# hybri.net
KiCad netlist of a schematic drawn in EAGLE
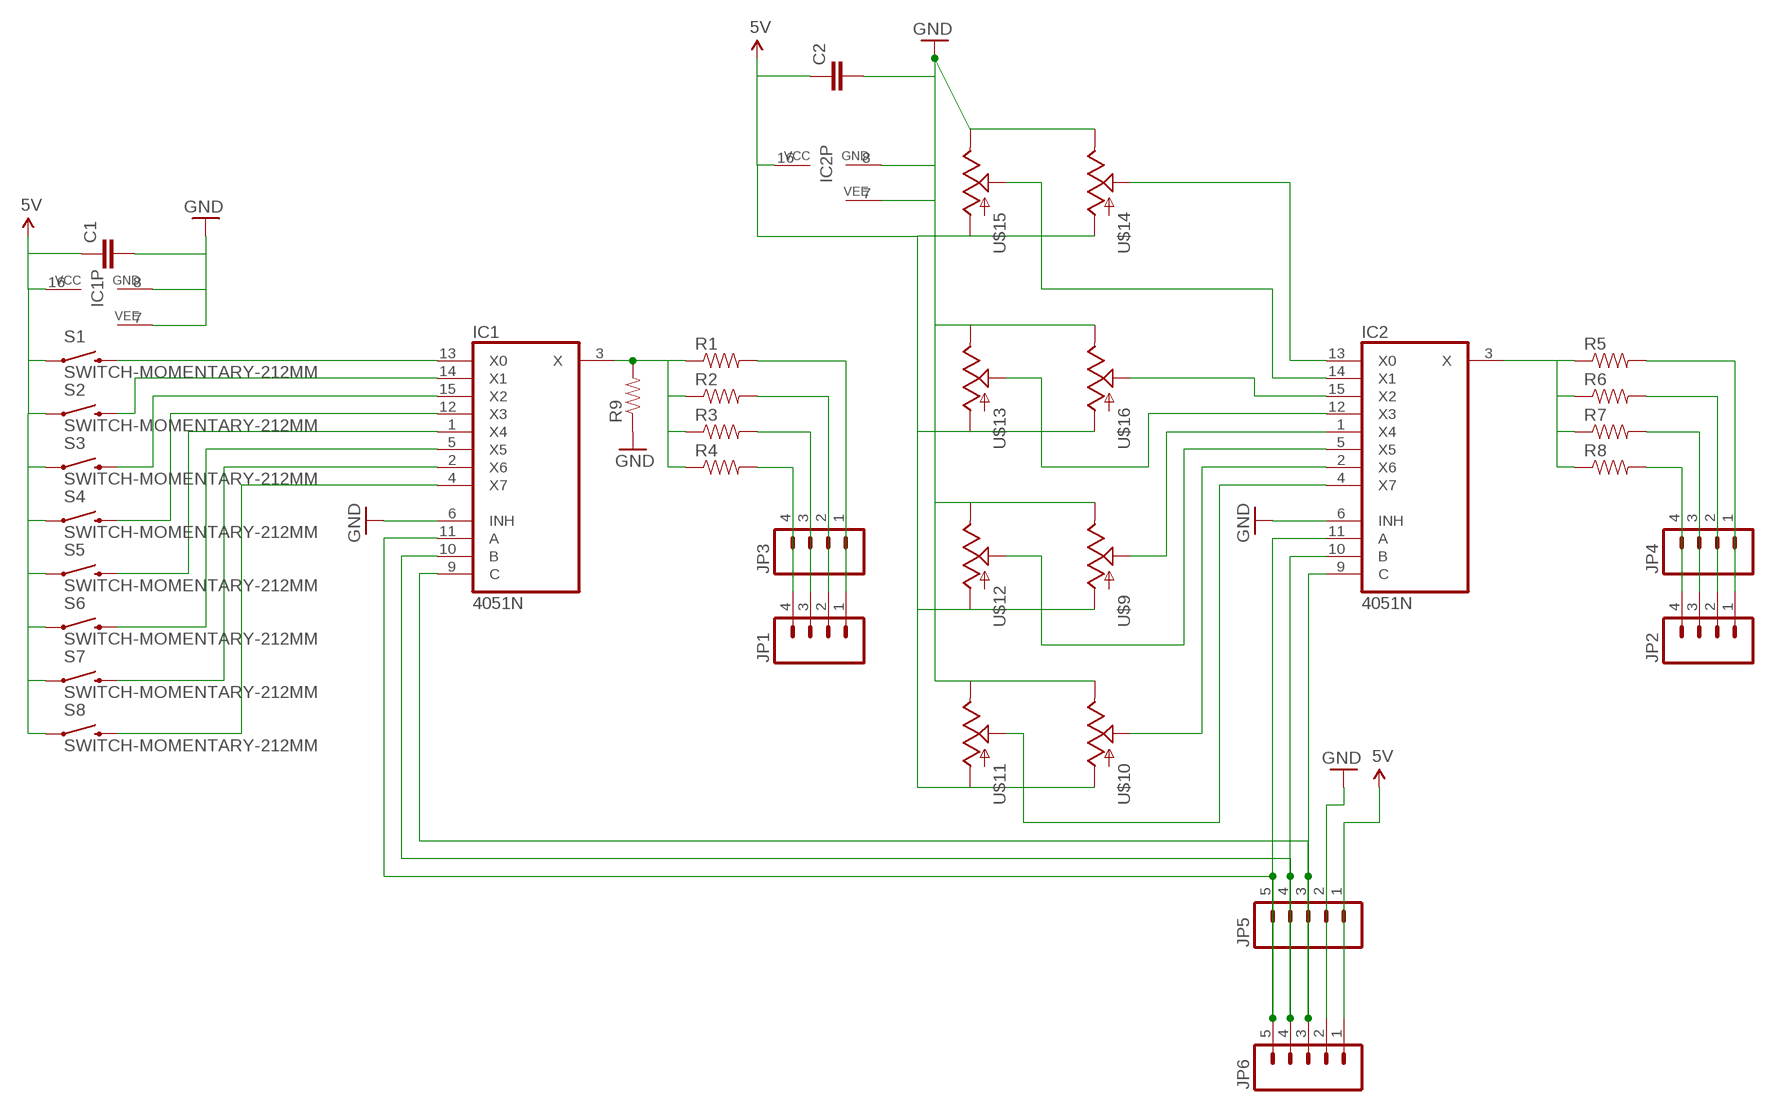
[diagram p0: schematic, sheet 1]

(export (version "E")
  (design (tool "Eeschema 10.0.6"))
  (components
    (comp (ref "C1")
      (value "CAPPTH")
      (footprint "eagle-import:CAP-PTH-SMALL")
      (libsource (lib "eagle-import") (part "CAPPTH"))
    )
    (comp (ref "C2")
      (value "CAPPTH")
      (footprint "eagle-import:CAP-PTH-SMALL")
      (libsource (lib "eagle-import") (part "CAPPTH"))
    )
    (comp (ref "IC1")
      (value "4051N")
      (footprint "eagle-import:DIL16")
      (libsource (lib "eagle-import") (part "4051N"))
    )
    (comp (ref "IC2")
      (value "4051N")
      (footprint "eagle-import:DIL16")
      (libsource (lib "eagle-import") (part "4051N"))
    )
    (comp (ref "JP1")
      (value "M04PTH")
      (footprint "eagle-import:1X04")
      (libsource (lib "eagle-import") (part "M04PTH"))
    )
    (comp (ref "JP2")
      (value "M04PTH")
      (footprint "eagle-import:1X04")
      (libsource (lib "eagle-import") (part "M04PTH"))
    )
    (comp (ref "JP3")
      (value "M04PTH")
      (footprint "eagle-import:1X04")
      (libsource (lib "eagle-import") (part "M04PTH"))
    )
    (comp (ref "JP4")
      (value "M04PTH")
      (footprint "eagle-import:1X04")
      (libsource (lib "eagle-import") (part "M04PTH"))
    )
    (comp (ref "JP5")
      (value "M05PTH")
      (footprint "eagle-import:1X05")
      (libsource (lib "eagle-import") (part "M05PTH"))
    )
    (comp (ref "JP6")
      (value "M05PTH")
      (footprint "eagle-import:1X05")
      (libsource (lib "eagle-import") (part "M05PTH"))
    )
    (comp (ref "R1")
      (value "RESISTORAXIAL-0.3")
      (footprint "eagle-import:AXIAL-0.3")
      (libsource (lib "eagle-import") (part "RESISTORAXIAL-0.3"))
    )
    (comp (ref "R2")
      (value "RESISTORAXIAL-0.3")
      (footprint "eagle-import:AXIAL-0.3")
      (libsource (lib "eagle-import") (part "RESISTORAXIAL-0.3"))
    )
    (comp (ref "R3")
      (value "RESISTORAXIAL-0.3")
      (footprint "eagle-import:AXIAL-0.3")
      (libsource (lib "eagle-import") (part "RESISTORAXIAL-0.3"))
    )
    (comp (ref "R4")
      (value "RESISTORAXIAL-0.3")
      (footprint "eagle-import:AXIAL-0.3")
      (libsource (lib "eagle-import") (part "RESISTORAXIAL-0.3"))
    )
    (comp (ref "R5")
      (value "RESISTORAXIAL-0.3")
      (footprint "eagle-import:AXIAL-0.3")
      (libsource (lib "eagle-import") (part "RESISTORAXIAL-0.3"))
    )
    (comp (ref "R6")
      (value "RESISTORAXIAL-0.3")
      (footprint "eagle-import:AXIAL-0.3")
      (libsource (lib "eagle-import") (part "RESISTORAXIAL-0.3"))
    )
    (comp (ref "R7")
      (value "RESISTORAXIAL-0.3")
      (footprint "eagle-import:AXIAL-0.3")
      (libsource (lib "eagle-import") (part "RESISTORAXIAL-0.3"))
    )
    (comp (ref "R8")
      (value "RESISTORAXIAL-0.3")
      (footprint "eagle-import:AXIAL-0.3")
      (libsource (lib "eagle-import") (part "RESISTORAXIAL-0.3"))
    )
    (comp (ref "R9")
      (value "RESISTORAXIAL-0.3")
      (footprint "eagle-import:AXIAL-0.3")
      (libsource (lib "eagle-import") (part "RESISTORAXIAL-0.3"))
    )
    (comp (ref "S1")
      (value "SWITCH-MOMENTARY-212MM")
      (footprint "eagle-import:TACTILE-PTH-12MM")
      (libsource (lib "eagle-import") (part "SWITCH-MOMENTARY-212MM"))
    )
    (comp (ref "S2")
      (value "SWITCH-MOMENTARY-212MM")
      (footprint "eagle-import:TACTILE-PTH-12MM")
      (libsource (lib "eagle-import") (part "SWITCH-MOMENTARY-212MM"))
    )
    (comp (ref "S3")
      (value "SWITCH-MOMENTARY-212MM")
      (footprint "eagle-import:TACTILE-PTH-12MM")
      (libsource (lib "eagle-import") (part "SWITCH-MOMENTARY-212MM"))
    )
    (comp (ref "S4")
      (value "SWITCH-MOMENTARY-212MM")
      (footprint "eagle-import:TACTILE-PTH-12MM")
      (libsource (lib "eagle-import") (part "SWITCH-MOMENTARY-212MM"))
    )
    (comp (ref "S5")
      (value "SWITCH-MOMENTARY-212MM")
      (footprint "eagle-import:TACTILE-PTH-12MM")
      (libsource (lib "eagle-import") (part "SWITCH-MOMENTARY-212MM"))
    )
    (comp (ref "S6")
      (value "SWITCH-MOMENTARY-212MM")
      (footprint "eagle-import:TACTILE-PTH-12MM")
      (libsource (lib "eagle-import") (part "SWITCH-MOMENTARY-212MM"))
    )
    (comp (ref "S7")
      (value "SWITCH-MOMENTARY-212MM")
      (footprint "eagle-import:TACTILE-PTH-12MM")
      (libsource (lib "eagle-import") (part "SWITCH-MOMENTARY-212MM"))
    )
    (comp (ref "S8")
      (value "SWITCH-MOMENTARY-212MM")
      (footprint "eagle-import:TACTILE-PTH-12MM")
      (libsource (lib "eagle-import") (part "SWITCH-MOMENTARY-212MM"))
    )
    (comp (ref "U$9")
      (value "POT")
      (footprint "eagle-import:ALPS_POT")
      (libsource (lib "eagle-import") (part "POT"))
    )
    (comp (ref "U$10")
      (value "POT")
      (footprint "eagle-import:ALPS_POT")
      (libsource (lib "eagle-import") (part "POT"))
    )
    (comp (ref "U$11")
      (value "POT")
      (footprint "eagle-import:ALPS_POT")
      (libsource (lib "eagle-import") (part "POT"))
    )
    (comp (ref "U$12")
      (value "POT")
      (footprint "eagle-import:ALPS_POT")
      (libsource (lib "eagle-import") (part "POT"))
    )
    (comp (ref "U$13")
      (value "POT")
      (footprint "eagle-import:ALPS_POT")
      (libsource (lib "eagle-import") (part "POT"))
    )
    (comp (ref "U$14")
      (value "POT")
      (footprint "eagle-import:ALPS_POT")
      (libsource (lib "eagle-import") (part "POT"))
    )
    (comp (ref "U$15")
      (value "POT")
      (footprint "eagle-import:ALPS_POT")
      (libsource (lib "eagle-import") (part "POT"))
    )
    (comp (ref "U$16")
      (value "POT")
      (footprint "eagle-import:ALPS_POT")
      (libsource (lib "eagle-import") (part "POT"))
    )
  )
  (nets
    (net (code "1") (name "5V") (class "Default")
      (node (ref "C1") (pin "1") (pinfunction "1_1") (pintype "passive"))
      (node (ref "C2") (pin "1") (pinfunction "1_1") (pintype "passive"))
      (node (ref "IC1") (pin "16") (pinfunction "VCC_16") (pintype "power_in"))
      (node (ref "IC2") (pin "16") (pinfunction "VCC_16") (pintype "power_in"))
      (node (ref "JP5") (pin "1") (pinfunction "1_1") (pintype "passive"))
      (node (ref "JP6") (pin "1") (pinfunction "1_1") (pintype "passive"))
      (node (ref "S1") (pin "1") (pinfunction "1_1") (pintype "passive"))
      (node (ref "S2") (pin "1") (pinfunction "1_1") (pintype "passive"))
      (node (ref "S3") (pin "1") (pinfunction "1_1") (pintype "passive"))
      (node (ref "S4") (pin "1") (pinfunction "1_1") (pintype "passive"))
      (node (ref "S5") (pin "1") (pinfunction "1_1") (pintype "passive"))
      (node (ref "S6") (pin "1") (pinfunction "1_1") (pintype "passive"))
      (node (ref "S7") (pin "1") (pinfunction "1_1") (pintype "passive"))
      (node (ref "S8") (pin "1") (pinfunction "1_1") (pintype "passive"))
      (node (ref "U$10") (pin "P$3") (pinfunction "A_P$3") (pintype "passive"))
      (node (ref "U$11") (pin "P$3") (pinfunction "A_P$3") (pintype "passive"))
      (node (ref "U$12") (pin "P$3") (pinfunction "A_P$3") (pintype "passive"))
      (node (ref "U$13") (pin "P$3") (pinfunction "A_P$3") (pintype "passive"))
      (node (ref "U$14") (pin "P$3") (pinfunction "A_P$3") (pintype "passive"))
      (node (ref "U$15") (pin "P$3") (pinfunction "A_P$3") (pintype "passive"))
      (node (ref "U$16") (pin "P$3") (pinfunction "A_P$3") (pintype "passive"))
      (node (ref "U$9") (pin "P$3") (pinfunction "A_P$3") (pintype "passive"))
    )
    (net (code "2") (name "GND") (class "Default")
      (node (ref "C1") (pin "2") (pinfunction "2_2") (pintype "passive"))
      (node (ref "C2") (pin "2") (pinfunction "2_2") (pintype "passive"))
      (node (ref "IC1") (pin "6") (pinfunction "INH_6") (pintype "input"))
      (node (ref "IC1") (pin "7") (pinfunction "VEE_7") (pintype "power_in"))
      (node (ref "IC1") (pin "8") (pinfunction "GND_8") (pintype "power_in"))
      (node (ref "IC2") (pin "6") (pinfunction "INH_6") (pintype "input"))
      (node (ref "IC2") (pin "7") (pinfunction "VEE_7") (pintype "power_in"))
      (node (ref "IC2") (pin "8") (pinfunction "GND_8") (pintype "power_in"))
      (node (ref "JP5") (pin "2") (pinfunction "2_2") (pintype "passive"))
      (node (ref "JP6") (pin "2") (pinfunction "2_2") (pintype "passive"))
      (node (ref "R9") (pin "P$1") (pinfunction "1_P$1") (pintype "passive"))
      (node (ref "U$10") (pin "P$1") (pinfunction "E_P$1") (pintype "passive"))
      (node (ref "U$11") (pin "P$1") (pinfunction "E_P$1") (pintype "passive"))
      (node (ref "U$12") (pin "P$1") (pinfunction "E_P$1") (pintype "passive"))
      (node (ref "U$13") (pin "P$1") (pinfunction "E_P$1") (pintype "passive"))
      (node (ref "U$14") (pin "P$1") (pinfunction "E_P$1") (pintype "passive"))
      (node (ref "U$15") (pin "P$1") (pinfunction "E_P$1") (pintype "passive"))
      (node (ref "U$16") (pin "P$1") (pinfunction "E_P$1") (pintype "passive"))
      (node (ref "U$9") (pin "P$1") (pinfunction "E_P$1") (pintype "passive"))
    )
    (net (code "3") (name "Net-(IC1A-A)") (class "Default")
      (node (ref "IC1") (pin "11") (pinfunction "A_11") (pintype "input"))
      (node (ref "IC2") (pin "11") (pinfunction "A_11") (pintype "input"))
      (node (ref "JP5") (pin "5") (pinfunction "5_5") (pintype "passive"))
      (node (ref "JP6") (pin "5") (pinfunction "5_5") (pintype "passive"))
    )
    (net (code "4") (name "Net-(IC1A-B)") (class "Default")
      (node (ref "IC1") (pin "10") (pinfunction "B_10") (pintype "input"))
      (node (ref "IC2") (pin "10") (pinfunction "B_10") (pintype "input"))
      (node (ref "JP5") (pin "4") (pinfunction "4_4") (pintype "passive"))
      (node (ref "JP6") (pin "4") (pinfunction "4_4") (pintype "passive"))
    )
    (net (code "5") (name "Net-(IC1A-C)") (class "Default")
      (node (ref "IC1") (pin "9") (pinfunction "C_9") (pintype "input"))
      (node (ref "IC2") (pin "9") (pinfunction "C_9") (pintype "input"))
      (node (ref "JP5") (pin "3") (pinfunction "3_3") (pintype "passive"))
      (node (ref "JP6") (pin "3") (pinfunction "3_3") (pintype "passive"))
    )
    (net (code "6") (name "Net-(IC1A-X)") (class "Default")
      (node (ref "IC1") (pin "3") (pinfunction "X_3") (pintype "bidirectional"))
      (node (ref "R1") (pin "P$1") (pinfunction "1_P$1") (pintype "passive"))
      (node (ref "R2") (pin "P$1") (pinfunction "1_P$1") (pintype "passive"))
      (node (ref "R3") (pin "P$1") (pinfunction "1_P$1") (pintype "passive"))
      (node (ref "R4") (pin "P$1") (pinfunction "1_P$1") (pintype "passive"))
      (node (ref "R9") (pin "P$2") (pinfunction "2_P$2") (pintype "passive"))
    )
    (net (code "7") (name "Net-(IC1A-X0)") (class "Default")
      (node (ref "IC1") (pin "13") (pinfunction "X0_13") (pintype "bidirectional"))
      (node (ref "S1") (pin "3") (pinfunction "2_3") (pintype "passive"))
    )
    (net (code "8") (name "Net-(IC1A-X1)") (class "Default")
      (node (ref "IC1") (pin "14") (pinfunction "X1_14") (pintype "bidirectional"))
      (node (ref "S2") (pin "3") (pinfunction "2_3") (pintype "passive"))
    )
    (net (code "9") (name "Net-(IC1A-X2)") (class "Default")
      (node (ref "IC1") (pin "15") (pinfunction "X2_15") (pintype "bidirectional"))
      (node (ref "S3") (pin "3") (pinfunction "2_3") (pintype "passive"))
    )
    (net (code "10") (name "Net-(IC1A-X3)") (class "Default")
      (node (ref "IC1") (pin "12") (pinfunction "X3_12") (pintype "bidirectional"))
      (node (ref "S4") (pin "3") (pinfunction "2_3") (pintype "passive"))
    )
    (net (code "11") (name "Net-(IC1A-X4)") (class "Default")
      (node (ref "IC1") (pin "1") (pinfunction "X4_1") (pintype "bidirectional"))
      (node (ref "S5") (pin "3") (pinfunction "2_3") (pintype "passive"))
    )
    (net (code "12") (name "Net-(IC1A-X5)") (class "Default")
      (node (ref "IC1") (pin "5") (pinfunction "X5_5") (pintype "bidirectional"))
      (node (ref "S6") (pin "3") (pinfunction "2_3") (pintype "passive"))
    )
    (net (code "13") (name "Net-(IC1A-X6)") (class "Default")
      (node (ref "IC1") (pin "2") (pinfunction "X6_2") (pintype "bidirectional"))
      (node (ref "S7") (pin "3") (pinfunction "2_3") (pintype "passive"))
    )
    (net (code "14") (name "Net-(IC1A-X7)") (class "Default")
      (node (ref "IC1") (pin "4") (pinfunction "X7_4") (pintype "bidirectional"))
      (node (ref "S8") (pin "3") (pinfunction "2_3") (pintype "passive"))
    )
    (net (code "15") (name "Net-(IC2A-X)") (class "Default")
      (node (ref "IC2") (pin "3") (pinfunction "X_3") (pintype "bidirectional"))
      (node (ref "R5") (pin "P$1") (pinfunction "1_P$1") (pintype "passive"))
      (node (ref "R6") (pin "P$1") (pinfunction "1_P$1") (pintype "passive"))
      (node (ref "R7") (pin "P$1") (pinfunction "1_P$1") (pintype "passive"))
      (node (ref "R8") (pin "P$1") (pinfunction "1_P$1") (pintype "passive"))
    )
    (net (code "16") (name "Net-(IC2A-X0)") (class "Default")
      (node (ref "IC2") (pin "13") (pinfunction "X0_13") (pintype "bidirectional"))
      (node (ref "U$14") (pin "P$2") (pinfunction "S_P$2") (pintype "passive"))
    )
    (net (code "17") (name "Net-(IC2A-X1)") (class "Default")
      (node (ref "IC2") (pin "14") (pinfunction "X1_14") (pintype "bidirectional"))
      (node (ref "U$15") (pin "P$2") (pinfunction "S_P$2") (pintype "passive"))
    )
    (net (code "18") (name "Net-(IC2A-X2)") (class "Default")
      (node (ref "IC2") (pin "15") (pinfunction "X2_15") (pintype "bidirectional"))
      (node (ref "U$16") (pin "P$2") (pinfunction "S_P$2") (pintype "passive"))
    )
    (net (code "19") (name "Net-(IC2A-X3)") (class "Default")
      (node (ref "IC2") (pin "12") (pinfunction "X3_12") (pintype "bidirectional"))
      (node (ref "U$13") (pin "P$2") (pinfunction "S_P$2") (pintype "passive"))
    )
    (net (code "20") (name "Net-(IC2A-X4)") (class "Default")
      (node (ref "IC2") (pin "1") (pinfunction "X4_1") (pintype "bidirectional"))
      (node (ref "U$9") (pin "P$2") (pinfunction "S_P$2") (pintype "passive"))
    )
    (net (code "21") (name "Net-(IC2A-X5)") (class "Default")
      (node (ref "IC2") (pin "5") (pinfunction "X5_5") (pintype "bidirectional"))
      (node (ref "U$12") (pin "P$2") (pinfunction "S_P$2") (pintype "passive"))
    )
    (net (code "22") (name "Net-(IC2A-X6)") (class "Default")
      (node (ref "IC2") (pin "2") (pinfunction "X6_2") (pintype "bidirectional"))
      (node (ref "U$10") (pin "P$2") (pinfunction "S_P$2") (pintype "passive"))
    )
    (net (code "23") (name "Net-(IC2A-X7)") (class "Default")
      (node (ref "IC2") (pin "4") (pinfunction "X7_4") (pintype "bidirectional"))
      (node (ref "U$11") (pin "P$2") (pinfunction "S_P$2") (pintype "passive"))
    )
    (net (code "24") (name "Net-(R1-2)") (class "Default")
      (node (ref "JP1") (pin "1") (pinfunction "1_1") (pintype "passive"))
      (node (ref "JP3") (pin "1") (pinfunction "1_1") (pintype "passive"))
      (node (ref "R1") (pin "P$2") (pinfunction "2_P$2") (pintype "passive"))
    )
    (net (code "25") (name "Net-(R2-2)") (class "Default")
      (node (ref "JP1") (pin "2") (pinfunction "2_2") (pintype "passive"))
      (node (ref "JP3") (pin "2") (pinfunction "2_2") (pintype "passive"))
      (node (ref "R2") (pin "P$2") (pinfunction "2_P$2") (pintype "passive"))
    )
    (net (code "26") (name "Net-(R3-2)") (class "Default")
      (node (ref "JP1") (pin "3") (pinfunction "3_3") (pintype "passive"))
      (node (ref "JP3") (pin "3") (pinfunction "3_3") (pintype "passive"))
      (node (ref "R3") (pin "P$2") (pinfunction "2_P$2") (pintype "passive"))
    )
    (net (code "27") (name "Net-(R4-2)") (class "Default")
      (node (ref "JP1") (pin "4") (pinfunction "4_4") (pintype "passive"))
      (node (ref "JP3") (pin "4") (pinfunction "4_4") (pintype "passive"))
      (node (ref "R4") (pin "P$2") (pinfunction "2_P$2") (pintype "passive"))
    )
    (net (code "28") (name "Net-(R5-2)") (class "Default")
      (node (ref "JP2") (pin "1") (pinfunction "1_1") (pintype "passive"))
      (node (ref "JP4") (pin "1") (pinfunction "1_1") (pintype "passive"))
      (node (ref "R5") (pin "P$2") (pinfunction "2_P$2") (pintype "passive"))
    )
    (net (code "29") (name "Net-(R6-2)") (class "Default")
      (node (ref "JP2") (pin "2") (pinfunction "2_2") (pintype "passive"))
      (node (ref "JP4") (pin "2") (pinfunction "2_2") (pintype "passive"))
      (node (ref "R6") (pin "P$2") (pinfunction "2_P$2") (pintype "passive"))
    )
    (net (code "30") (name "Net-(R7-2)") (class "Default")
      (node (ref "JP2") (pin "3") (pinfunction "3_3") (pintype "passive"))
      (node (ref "JP4") (pin "3") (pinfunction "3_3") (pintype "passive"))
      (node (ref "R7") (pin "P$2") (pinfunction "2_P$2") (pintype "passive"))
    )
    (net (code "31") (name "Net-(R8-2)") (class "Default")
      (node (ref "JP2") (pin "4") (pinfunction "4_4") (pintype "passive"))
      (node (ref "JP4") (pin "4") (pinfunction "4_4") (pintype "passive"))
      (node (ref "R8") (pin "P$2") (pinfunction "2_P$2") (pintype "passive"))
    )
  )
)
